# Sheet1.net
KiCad netlist of a schematic drawn in Altium Designer
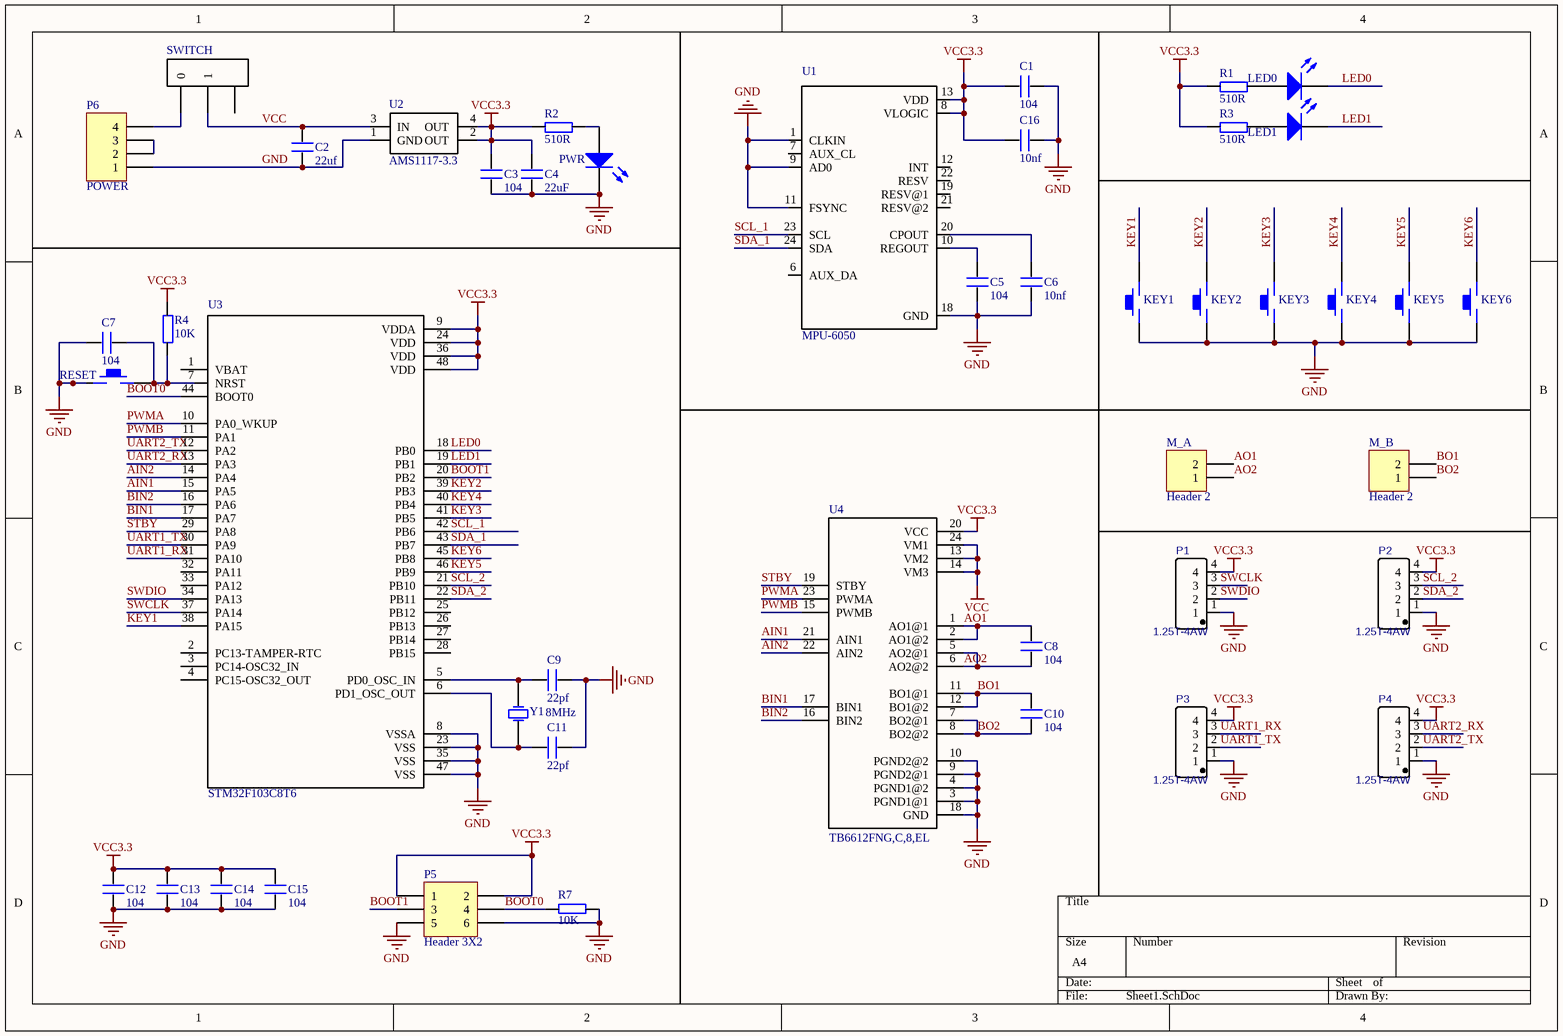
[diagram p0: Sheet1.SchDoc]

(export (version "E")
  (design (tool "Eeschema 10.0.6"))
  (components
    (comp (ref "1")
      (value "LED0")
      (footprint "*0805")
      (description "Typical RED, GREEN, YELLOW, AMBER GaAs LED")
      (fields (field (name "PUBLISHER") "Altium Limited"))
      (libsource (lib "Schlib1") (part "LED2"))
    )
    (comp (ref "2")
      (value "LED1")
      (footprint "*0805")
      (description "Typical RED, GREEN, YELLOW, AMBER GaAs LED")
      (fields (field (name "PUBLISHER") "Altium Limited"))
      (libsource (lib "Schlib1") (part "LED2"))
    )
    (comp (ref "C1") (value "104") (footprint "*0805") (libsource (lib "Schlib1") (part "C")))
    (comp (ref "C2") (value "22uf") (footprint "*0805") (libsource (lib "Schlib1") (part "C")))
    (comp (ref "C3") (value "104") (footprint "*0805") (libsource (lib "Schlib1") (part "C")))
    (comp (ref "C4") (value "22uF") (footprint "*0805") (libsource (lib "Schlib1") (part "C")))
    (comp (ref "C5") (value "104") (footprint "*0805") (libsource (lib "Schlib1") (part "C")))
    (comp (ref "C6") (value "10nf") (footprint "*0805") (libsource (lib "Schlib1") (part "C")))
    (comp (ref "C7") (value "104") (footprint "*0805") (libsource (lib "Schlib1") (part "C")))
    (comp (ref "C8") (value "104") (footprint "*0805") (libsource (lib "Schlib1") (part "C")))
    (comp (ref "C9") (value "22pf") (footprint "*0805") (libsource (lib "Schlib1") (part "C")))
    (comp (ref "C10") (value "104") (footprint "*0805") (libsource (lib "Schlib1") (part "C")))
    (comp (ref "C11") (value "22pf") (footprint "*0805") (libsource (lib "Schlib1") (part "C")))
    (comp (ref "C12") (value "104") (footprint "*0805") (libsource (lib "Schlib1") (part "C")))
    (comp (ref "C13") (value "104") (footprint "*0805") (libsource (lib "Schlib1") (part "C")))
    (comp (ref "C14") (value "104") (footprint "*0805") (libsource (lib "Schlib1") (part "C")))
    (comp (ref "C15") (value "104") (footprint "*0805") (libsource (lib "Schlib1") (part "C")))
    (comp (ref "C16") (value "10nf") (footprint "*0805") (libsource (lib "Schlib1") (part "C")))
    (comp (ref "KEY1") (value "KEY") (footprint "*KEY") (libsource (lib "Schlib1") (part "KEY")))
    (comp (ref "KEY2") (value "KEY") (footprint "*KEY") (libsource (lib "Schlib1") (part "KEY")))
    (comp (ref "KEY3") (value "KEY") (footprint "*KEY") (libsource (lib "Schlib1") (part "KEY")))
    (comp (ref "KEY4") (value "KEY") (footprint "*KEY") (libsource (lib "Schlib1") (part "KEY")))
    (comp (ref "KEY5") (value "KEY") (footprint "*KEY") (libsource (lib "Schlib1") (part "KEY")))
    (comp (ref "KEY6") (value "KEY") (footprint "*KEY") (libsource (lib "Schlib1") (part "KEY")))
    (comp (ref "LED")
      (value "PWR")
      (footprint "*0805")
      (description "Typical RED, GREEN, YELLOW, AMBER GaAs LED")
      (fields (field (name "PUBLISHER") "Altium Limited"))
      (libsource (lib "Schlib1") (part "LED2"))
    )
    (comp (ref "M_A")
      (value "Header 2")
      (footprint "HDR1X2")
      (description "Header, 2-Pin")
      (fields (field (name "PUBLISHER") "Altium Limited"))
      (libsource (lib "Miscellaneous Connectors") (part "Header 2"))
    )
    (comp (ref "M_B")
      (value "Header 2")
      (footprint "HDR1X2")
      (description "Header, 2-Pin")
      (fields (field (name "PUBLISHER") "Altium Limited"))
      (libsource (lib "Miscellaneous Connectors") (part "Header 2"))
    )
    (comp (ref "P1")
      (value "1.25T-4AW")
      (footprint "*1.25T-4AW")
      (fields (field (name "BOM_SUPPLIER PART") "C14939"))
      (libsource (lib "Schlib1") (part "1.25T-4AW"))
    )
    (comp (ref "P2")
      (value "1.25T-4AW")
      (footprint "*1.25T-4AW")
      (fields (field (name "BOM_SUPPLIER PART") "C14939"))
      (libsource (lib "Schlib1") (part "1.25T-4AW"))
    )
    (comp (ref "P3")
      (value "1.25T-4AW")
      (footprint "*1.25T-4AW")
      (fields (field (name "BOM_SUPPLIER PART") "C14939"))
      (libsource (lib "Schlib1") (part "1.25T-4AW"))
    )
    (comp (ref "P4")
      (value "1.25T-4AW")
      (footprint "*1.25T-4AW")
      (fields (field (name "BOM_SUPPLIER PART") "C14939"))
      (libsource (lib "Schlib1") (part "1.25T-4AW"))
    )
    (comp (ref "P5")
      (value "Header 3X2")
      (footprint "HDR2X3")
      (description "Header, 3-Pin, Dual row")
      (fields (field (name "PUBLISHER") "Altium Limited"))
      (libsource (lib "Miscellaneous Connectors") (part "Header 3X2"))
    )
    (comp (ref "P6")
      (value "POWER")
      (footprint "HDR1X4")
      (description "Header, 4-Pin")
      (fields (field (name "PUBLISHER") "Altium Limited"))
      (libsource (lib "Miscellaneous Connectors") (part "Header 4"))
    )
    (comp (ref "R1") (value "510R") (footprint "*0805") (libsource (lib "Schlib1") (part "R")))
    (comp (ref "R2") (value "510R") (footprint "*0805") (libsource (lib "Schlib1") (part "R")))
    (comp (ref "R3") (value "510R") (footprint "*0805") (libsource (lib "Schlib1") (part "R")))
    (comp (ref "R4") (value "10K") (footprint "*0805") (libsource (lib "Schlib1") (part "R")))
    (comp (ref "R7") (value "10K") (footprint "*0805") (libsource (lib "Schlib1") (part "R")))
    (comp (ref "RESET") (value "KEY") (footprint "*KEY") (libsource (lib "") (part "KEY_1")))
    (comp (ref "SWITCH") (value "SWITCH") (footprint "*SWITCH") (libsource (lib "Schlib1") (part "SWITCH")))
    (comp (ref "U1")
      (value "MPU-6050")
      (footprint "*QFN50P400X400X95-24N")
      (description "3-axis gyroscope, 3-axis accelerometer in a 4x4x0.9 housing")
      (fields (field (name "DIGI-KEY_PART_NUMBER") "1428-1007-1-ND") (field (name "MF") "TDK InvenSense"))
      (libsource (lib "Schlib1") (part "MPU-6050"))
    )
    (comp (ref "U2")
      (value "AMS1117-3.3")
      (footprint "*AMS1117")
      (libsource (lib "Schlib1") (part "AMS1117"))
    )
    (comp (ref "U3")
      (value "STM32F103C8T6")
      (footprint "*QFP50P900X900X160-48N")
      (fields (field (name "MF") "STMicroelectronics"))
      (libsource (lib "Schlib1") (part "STM32F103C8T6"))
    )
    (comp (ref "U4")
      (value "TB6612FNG,C,8,EL")
      (footprint "*SOP65P760X160-24N")
      (description "Stepping Motor Driver Ic Unipolor Copper Wire 8")
      (fields (field (name "DIGI-KEY_PART_NUMBER") "TB6612FNGC8ELCT-ND") (field (name "MF") "Toshiba"))
      (libsource (lib "Schlib1") (part "TB6612FNG,C,8,EL"))
    )
    (comp (ref "Y1")
      (value "8MHz")
      (footprint "*XTAL")
      (description "Crystal Oscillator")
      (fields (field (name "PUBLISHER") "Altium Limited"))
      (libsource (lib "Schlib1") (part "XTAL"))
    )
  )
  (nets
    (net (code "1") (name "/AIN1") (class "Default")
      (node (ref "U3") (pin "15") (pinfunction "PA5_15") (pintype "passive"))
      (node (ref "U4") (pin "21") (pinfunction "AIN1_21") (pintype "passive"))
    )
    (net (code "2") (name "/AIN2") (class "Default")
      (node (ref "U3") (pin "14") (pinfunction "PA4_14") (pintype "passive"))
      (node (ref "U4") (pin "22") (pinfunction "AIN2_22") (pintype "passive"))
    )
    (net (code "3") (name "/AO1") (class "Default")
      (node (ref "C8") (pin "2") (pintype "passive"))
      (node (ref "M_A") (pin "2") (pinfunction "2_2") (pintype "passive"))
      (node (ref "U4") (pin "1") (pinfunction "AO1@1_1") (pintype "passive"))
      (node (ref "U4") (pin "2") (pinfunction "AO1@2_2") (pintype "passive"))
    )
    (net (code "4") (name "/AO2") (class "Default")
      (node (ref "C8") (pin "1") (pintype "passive"))
      (node (ref "M_A") (pin "1") (pinfunction "1_1") (pintype "passive"))
      (node (ref "U4") (pin "5") (pinfunction "AO2@1_5") (pintype "passive"))
      (node (ref "U4") (pin "6") (pinfunction "AO2@2_6") (pintype "passive"))
    )
    (net (code "5") (name "/BIN1") (class "Default")
      (node (ref "U3") (pin "17") (pinfunction "PA7_17") (pintype "passive"))
      (node (ref "U4") (pin "17") (pinfunction "BIN1_17") (pintype "passive"))
    )
    (net (code "6") (name "/BIN2") (class "Default")
      (node (ref "U3") (pin "16") (pinfunction "PA6_16") (pintype "passive"))
      (node (ref "U4") (pin "16") (pinfunction "BIN2_16") (pintype "passive"))
    )
    (net (code "7") (name "/BO1") (class "Default")
      (node (ref "C10") (pin "2") (pintype "passive"))
      (node (ref "M_B") (pin "2") (pinfunction "2_2") (pintype "passive"))
      (node (ref "U4") (pin "11") (pinfunction "BO1@1_11") (pintype "passive"))
      (node (ref "U4") (pin "12") (pinfunction "BO1@2_12") (pintype "passive"))
    )
    (net (code "8") (name "/BO2") (class "Default")
      (node (ref "C10") (pin "1") (pintype "passive"))
      (node (ref "M_B") (pin "1") (pinfunction "1_1") (pintype "passive"))
      (node (ref "U4") (pin "7") (pinfunction "BO2@1_7") (pintype "passive"))
      (node (ref "U4") (pin "8") (pinfunction "BO2@2_8") (pintype "passive"))
    )
    (net (code "9") (name "/BOOT0") (class "Default")
      (node (ref "P5") (pin "4") (pinfunction "4_4") (pintype "passive"))
      (node (ref "R7") (pin "2") (pintype "passive"))
      (node (ref "U3") (pin "44") (pinfunction "BOOT0_44") (pintype "passive"))
    )
    (net (code "10") (name "/BOOT1") (class "Default")
      (node (ref "P5") (pin "3") (pinfunction "3_3") (pintype "passive"))
      (node (ref "U3") (pin "20") (pinfunction "PB2_20") (pintype "passive"))
    )
    (net (code "11") (name "/KEY1") (class "Default")
      (node (ref "KEY1") (pin "2") (pinfunction "2_2") (pintype "passive"))
      (node (ref "U3") (pin "38") (pinfunction "PA15_38") (pintype "passive"))
    )
    (net (code "12") (name "/KEY2") (class "Default")
      (node (ref "KEY2") (pin "2") (pinfunction "2_2") (pintype "passive"))
      (node (ref "U3") (pin "39") (pinfunction "PB3_39") (pintype "passive"))
    )
    (net (code "13") (name "/KEY3") (class "Default")
      (node (ref "KEY3") (pin "2") (pinfunction "2_2") (pintype "passive"))
      (node (ref "U3") (pin "41") (pinfunction "PB5_41") (pintype "passive"))
    )
    (net (code "14") (name "/KEY4") (class "Default")
      (node (ref "KEY4") (pin "2") (pinfunction "2_2") (pintype "passive"))
      (node (ref "U3") (pin "40") (pinfunction "PB4_40") (pintype "passive"))
    )
    (net (code "15") (name "/KEY5") (class "Default")
      (node (ref "KEY5") (pin "2") (pinfunction "2_2") (pintype "passive"))
      (node (ref "U3") (pin "46") (pinfunction "PB9_46") (pintype "passive"))
    )
    (net (code "16") (name "/KEY6") (class "Default")
      (node (ref "KEY6") (pin "2") (pinfunction "2_2") (pintype "passive"))
      (node (ref "U3") (pin "45") (pinfunction "PB8_45") (pintype "passive"))
    )
    (net (code "17") (name "/LED0") (class "Default")
      (node (ref "1") (pin "2") (pinfunction "K_2") (pintype "passive"))
      (node (ref "U3") (pin "18") (pinfunction "PB0_18") (pintype "passive"))
    )
    (net (code "18") (name "/LED1") (class "Default")
      (node (ref "2") (pin "2") (pinfunction "K_2") (pintype "passive"))
      (node (ref "U3") (pin "19") (pinfunction "PB1_19") (pintype "passive"))
    )
    (net (code "19") (name "/PWMA") (class "Default")
      (node (ref "U3") (pin "10") (pinfunction "PA0_WKUP_10") (pintype "passive"))
      (node (ref "U4") (pin "23") (pinfunction "PWMA_23") (pintype "passive"))
    )
    (net (code "20") (name "/PWMB") (class "Default")
      (node (ref "U3") (pin "11") (pinfunction "PA1_11") (pintype "passive"))
      (node (ref "U4") (pin "15") (pinfunction "PWMB_15") (pintype "passive"))
    )
    (net (code "21") (name "/SCL_1") (class "Default")
      (node (ref "U1") (pin "23") (pinfunction "SCL_23") (pintype "passive"))
      (node (ref "U3") (pin "42") (pinfunction "PB6_42") (pintype "passive"))
    )
    (net (code "22") (name "/SCL_2") (class "Default")
      (node (ref "P2") (pin "3") (pinfunction "3_3") (pintype "passive"))
      (node (ref "U3") (pin "21") (pinfunction "PB10_21") (pintype "passive"))
    )
    (net (code "23") (name "/SDA_1") (class "Default")
      (node (ref "U1") (pin "24") (pinfunction "SDA_24") (pintype "passive"))
      (node (ref "U3") (pin "43") (pinfunction "PB7_43") (pintype "passive"))
    )
    (net (code "24") (name "/SDA_2") (class "Default")
      (node (ref "P2") (pin "2") (pinfunction "2_2") (pintype "passive"))
      (node (ref "U3") (pin "22") (pinfunction "PB11_22") (pintype "passive"))
    )
    (net (code "25") (name "/STBY") (class "Default")
      (node (ref "U3") (pin "29") (pinfunction "PA8_29") (pintype "passive"))
      (node (ref "U4") (pin "19") (pinfunction "STBY_19") (pintype "passive"))
    )
    (net (code "26") (name "/SWCLK") (class "Default")
      (node (ref "P1") (pin "3") (pinfunction "3_3") (pintype "passive"))
      (node (ref "U3") (pin "37") (pinfunction "PA14_37") (pintype "passive"))
    )
    (net (code "27") (name "/SWDIO") (class "Default")
      (node (ref "P1") (pin "2") (pinfunction "2_2") (pintype "passive"))
      (node (ref "U3") (pin "34") (pinfunction "PA13_34") (pintype "passive"))
    )
    (net (code "28") (name "/UART1_RX") (class "Default")
      (node (ref "P3") (pin "3") (pinfunction "3_3") (pintype "passive"))
      (node (ref "U3") (pin "31") (pinfunction "PA10_31") (pintype "passive"))
    )
    (net (code "29") (name "/UART1_TX") (class "Default")
      (node (ref "P3") (pin "2") (pinfunction "2_2") (pintype "passive"))
      (node (ref "U3") (pin "30") (pinfunction "PA9_30") (pintype "passive"))
    )
    (net (code "30") (name "/UART2_RX") (class "Default")
      (node (ref "P4") (pin "3") (pinfunction "3_3") (pintype "passive"))
      (node (ref "U3") (pin "13") (pinfunction "PA3_13") (pintype "passive"))
    )
    (net (code "31") (name "/UART2_TX") (class "Default")
      (node (ref "P4") (pin "2") (pinfunction "2_2") (pintype "passive"))
      (node (ref "U3") (pin "12") (pinfunction "PA2_12") (pintype "passive"))
    )
    (net (code "32") (name "GND") (class "Default")
      (node (ref "C1") (pin "1") (pintype "passive"))
      (node (ref "C11") (pin "2") (pintype "passive"))
      (node (ref "C12") (pin "1") (pintype "passive"))
      (node (ref "C13") (pin "1") (pintype "passive"))
      (node (ref "C14") (pin "1") (pintype "passive"))
      (node (ref "C15") (pin "1") (pintype "passive"))
      (node (ref "C16") (pin "1") (pintype "passive"))
      (node (ref "C2") (pin "1") (pintype "passive"))
      (node (ref "C3") (pin "1") (pintype "passive"))
      (node (ref "C4") (pin "1") (pintype "passive"))
      (node (ref "C5") (pin "1") (pintype "passive"))
      (node (ref "C6") (pin "1") (pintype "passive"))
      (node (ref "C7") (pin "1") (pintype "passive"))
      (node (ref "C9") (pin "2") (pintype "passive"))
      (node (ref "KEY1") (pin "1") (pinfunction "1_1") (pintype "passive"))
      (node (ref "KEY2") (pin "1") (pinfunction "1_1") (pintype "passive"))
      (node (ref "KEY3") (pin "1") (pinfunction "1_1") (pintype "passive"))
      (node (ref "KEY4") (pin "1") (pinfunction "1_1") (pintype "passive"))
      (node (ref "KEY5") (pin "1") (pinfunction "1_1") (pintype "passive"))
      (node (ref "KEY6") (pin "1") (pinfunction "1_1") (pintype "passive"))
      (node (ref "LED") (pin "2") (pinfunction "K_2") (pintype "passive"))
      (node (ref "P1") (pin "1") (pinfunction "1_1") (pintype "passive"))
      (node (ref "P2") (pin "1") (pinfunction "1_1") (pintype "passive"))
      (node (ref "P3") (pin "1") (pinfunction "1_1") (pintype "passive"))
      (node (ref "P4") (pin "1") (pinfunction "1_1") (pintype "passive"))
      (node (ref "P5") (pin "5") (pinfunction "5_5") (pintype "passive"))
      (node (ref "P5") (pin "6") (pinfunction "6_6") (pintype "passive"))
      (node (ref "P6") (pin "1") (pinfunction "1_1") (pintype "passive"))
      (node (ref "R7") (pin "1") (pintype "passive"))
      (node (ref "RESET") (pin "1") (pinfunction "1_1") (pintype "passive"))
      (node (ref "U1") (pin "1") (pinfunction "CLKIN_1") (pintype "passive"))
      (node (ref "U1") (pin "11") (pinfunction "FSYNC_11") (pintype "passive"))
      (node (ref "U1") (pin "18") (pinfunction "GND_18") (pintype "passive"))
      (node (ref "U1") (pin "9") (pinfunction "AD0_9") (pintype "passive"))
      (node (ref "U2") (pin "1") (pinfunction "GND_1") (pintype "passive"))
      (node (ref "U3") (pin "23") (pinfunction "VSS_23") (pintype "passive"))
      (node (ref "U3") (pin "35") (pinfunction "VSS_35") (pintype "passive"))
      (node (ref "U3") (pin "47") (pinfunction "VSS_47") (pintype "passive"))
      (node (ref "U3") (pin "8") (pinfunction "VSSA_8") (pintype "passive"))
      (node (ref "U4") (pin "10") (pinfunction "PGND2@2_10") (pintype "passive"))
      (node (ref "U4") (pin "18") (pinfunction "GND_18") (pintype "passive"))
      (node (ref "U4") (pin "3") (pinfunction "PGND1@1_3") (pintype "passive"))
      (node (ref "U4") (pin "4") (pinfunction "PGND1@2_4") (pintype "passive"))
      (node (ref "U4") (pin "9") (pinfunction "PGND2@1_9") (pintype "passive"))
    )
    (net (code "33") (name "Net-(1-A)") (class "Default")
      (node (ref "1") (pin "1") (pinfunction "A_1") (pintype "passive"))
      (node (ref "R1") (pin "2") (pintype "passive"))
    )
    (net (code "34") (name "Net-(2-A)") (class "Default")
      (node (ref "2") (pin "1") (pinfunction "A_1") (pintype "passive"))
      (node (ref "R3") (pin "2") (pintype "passive"))
    )
    (net (code "35") (name "Net-(LED-A)") (class "Default")
      (node (ref "LED") (pin "1") (pinfunction "A_1") (pintype "passive"))
      (node (ref "R2") (pin "2") (pintype "passive"))
    )
    (net (code "36") (name "Net-(P6-Pad2)") (class "Default")
      (node (ref "P6") (pin "2") (pinfunction "2_2") (pintype "passive"))
      (node (ref "P6") (pin "3") (pinfunction "3_3") (pintype "passive"))
    )
    (net (code "37") (name "Net-(P6-Pad4)") (class "Default")
      (node (ref "P6") (pin "4") (pinfunction "4_4") (pintype "passive"))
      (node (ref "SWITCH") (pin "0") (pinfunction "0_0") (pintype "passive"))
    )
    (net (code "38") (name "Net-(U1-CPOUT)") (class "Default")
      (node (ref "C6") (pin "2") (pintype "passive"))
      (node (ref "U1") (pin "20") (pinfunction "CPOUT_20") (pintype "passive"))
    )
    (net (code "39") (name "Net-(U1-REGOUT)") (class "Default")
      (node (ref "C5") (pin "2") (pintype "passive"))
      (node (ref "U1") (pin "10") (pinfunction "REGOUT_10") (pintype "passive"))
    )
    (net (code "40") (name "Net-(U3-NRST)") (class "Default")
      (node (ref "C7") (pin "2") (pintype "passive"))
      (node (ref "R4") (pin "1") (pintype "passive"))
      (node (ref "RESET") (pin "2") (pinfunction "2_2") (pintype "passive"))
      (node (ref "U3") (pin "7") (pinfunction "NRST_7") (pintype "passive"))
    )
    (net (code "41") (name "Net-(U3-PD0_OSC_IN)") (class "Default")
      (node (ref "C9") (pin "1") (pintype "passive"))
      (node (ref "U3") (pin "5") (pinfunction "PD0_OSC_IN_5") (pintype "passive"))
      (node (ref "Y1") (pin "1") (pinfunction "OSC2_1") (pintype "passive"))
    )
    (net (code "42") (name "Net-(U3-PD1_OSC_OUT)") (class "Default")
      (node (ref "C11") (pin "1") (pintype "passive"))
      (node (ref "U3") (pin "6") (pinfunction "PD1_OSC_OUT_6") (pintype "passive"))
      (node (ref "Y1") (pin "0") (pinfunction "OSC1_0") (pintype "passive"))
    )
    (net (code "43") (name "VCC") (class "Default")
      (node (ref "C2") (pin "2") (pintype "passive"))
      (node (ref "SWITCH") (pin "1") (pinfunction "1_1") (pintype "passive"))
      (node (ref "U2") (pin "3") (pinfunction "IN_3") (pintype "passive"))
      (node (ref "U4") (pin "13") (pinfunction "VM2_13") (pintype "passive"))
      (node (ref "U4") (pin "14") (pinfunction "VM3_14") (pintype "passive"))
      (node (ref "U4") (pin "24") (pinfunction "VM1_24") (pintype "passive"))
    )
    (net (code "44") (name "VCC3.3") (class "Default")
      (node (ref "C1") (pin "2") (pintype "passive"))
      (node (ref "C12") (pin "2") (pintype "passive"))
      (node (ref "C13") (pin "2") (pintype "passive"))
      (node (ref "C14") (pin "2") (pintype "passive"))
      (node (ref "C15") (pin "2") (pintype "passive"))
      (node (ref "C16") (pin "2") (pintype "passive"))
      (node (ref "C3") (pin "2") (pintype "passive"))
      (node (ref "C4") (pin "2") (pintype "passive"))
      (node (ref "P1") (pin "4") (pinfunction "4_4") (pintype "passive"))
      (node (ref "P2") (pin "4") (pinfunction "4_4") (pintype "passive"))
      (node (ref "P3") (pin "4") (pinfunction "4_4") (pintype "passive"))
      (node (ref "P4") (pin "4") (pinfunction "4_4") (pintype "passive"))
      (node (ref "P5") (pin "1") (pinfunction "1_1") (pintype "passive"))
      (node (ref "P5") (pin "2") (pinfunction "2_2") (pintype "passive"))
      (node (ref "R1") (pin "1") (pintype "passive"))
      (node (ref "R2") (pin "1") (pintype "passive"))
      (node (ref "R3") (pin "1") (pintype "passive"))
      (node (ref "R4") (pin "2") (pintype "passive"))
      (node (ref "U1") (pin "13") (pinfunction "VDD_13") (pintype "passive"))
      (node (ref "U1") (pin "8") (pinfunction "VLOGIC_8") (pintype "passive"))
      (node (ref "U2") (pin "2") (pinfunction "OUT_2") (pintype "passive"))
      (node (ref "U2") (pin "4") (pinfunction "OUT_4") (pintype "passive"))
      (node (ref "U3") (pin "24") (pinfunction "VDD_24") (pintype "passive"))
      (node (ref "U3") (pin "36") (pinfunction "VDD_36") (pintype "passive"))
      (node (ref "U3") (pin "48") (pinfunction "VDD_48") (pintype "passive"))
      (node (ref "U3") (pin "9") (pinfunction "VDDA_9") (pintype "passive"))
      (node (ref "U4") (pin "20") (pinfunction "VCC_20") (pintype "passive"))
    )
    (net (code "45") (name "unconnected-(SWITCH-Pad2)") (class "Default")
      (node (ref "SWITCH") (pin "2") (pinfunction "2_2") (pintype "passive"))
    )
    (net (code "46") (name "unconnected-(U1-AUX_CL-Pad7)") (class "Default")
      (node (ref "U1") (pin "7") (pinfunction "AUX_CL_7") (pintype "passive"))
    )
    (net (code "47") (name "unconnected-(U1-AUX_DA-Pad6)") (class "Default")
      (node (ref "U1") (pin "6") (pinfunction "AUX_DA_6") (pintype "passive"))
    )
    (net (code "48") (name "unconnected-(U1-INT-Pad12)") (class "Default")
      (node (ref "U1") (pin "12") (pinfunction "INT_12") (pintype "passive"))
    )
    (net (code "49") (name "unconnected-(U1-RESV-Pad22)") (class "Default")
      (node (ref "U1") (pin "22") (pinfunction "RESV_22") (pintype "passive"))
    )
    (net (code "50") (name "unconnected-(U1-RESV@1-Pad19)") (class "Default")
      (node (ref "U1") (pin "19") (pinfunction "RESV@1_19") (pintype "passive"))
    )
    (net (code "51") (name "unconnected-(U1-RESV@2-Pad21)") (class "Default")
      (node (ref "U1") (pin "21") (pinfunction "RESV@2_21") (pintype "passive"))
    )
    (net (code "52") (name "unconnected-(U3-PA11-Pad32)") (class "Default")
      (node (ref "U3") (pin "32") (pinfunction "PA11_32") (pintype "passive"))
    )
    (net (code "53") (name "unconnected-(U3-PA12-Pad33)") (class "Default")
      (node (ref "U3") (pin "33") (pinfunction "PA12_33") (pintype "passive"))
    )
    (net (code "54") (name "unconnected-(U3-PB12-Pad25)") (class "Default")
      (node (ref "U3") (pin "25") (pinfunction "PB12_25") (pintype "passive"))
    )
    (net (code "55") (name "unconnected-(U3-PB13-Pad26)") (class "Default")
      (node (ref "U3") (pin "26") (pinfunction "PB13_26") (pintype "passive"))
    )
    (net (code "56") (name "unconnected-(U3-PB14-Pad27)") (class "Default")
      (node (ref "U3") (pin "27") (pinfunction "PB14_27") (pintype "passive"))
    )
    (net (code "57") (name "unconnected-(U3-PB15-Pad28)") (class "Default")
      (node (ref "U3") (pin "28") (pinfunction "PB15_28") (pintype "passive"))
    )
    (net (code "58") (name "unconnected-(U3-PC13-TAMPER-RTC-Pad2)") (class "Default")
      (node (ref "U3") (pin "2") (pinfunction "PC13-TAMPER-RTC_2") (pintype "passive"))
    )
    (net (code "59") (name "unconnected-(U3-PC14-OSC32_IN-Pad3)") (class "Default")
      (node (ref "U3") (pin "3") (pinfunction "PC14-OSC32_IN_3") (pintype "passive"))
    )
    (net (code "60") (name "unconnected-(U3-PC15-OSC32_OUT-Pad4)") (class "Default")
      (node (ref "U3") (pin "4") (pinfunction "PC15-OSC32_OUT_4") (pintype "passive"))
    )
    (net (code "61") (name "unconnected-(U3-VBAT-Pad1)") (class "Default")
      (node (ref "U3") (pin "1") (pinfunction "VBAT_1") (pintype "passive"))
    )
  )
)
